# Zio_Eink_Display_Red_2_9.net
KiCad netlist of a schematic drawn in EAGLE
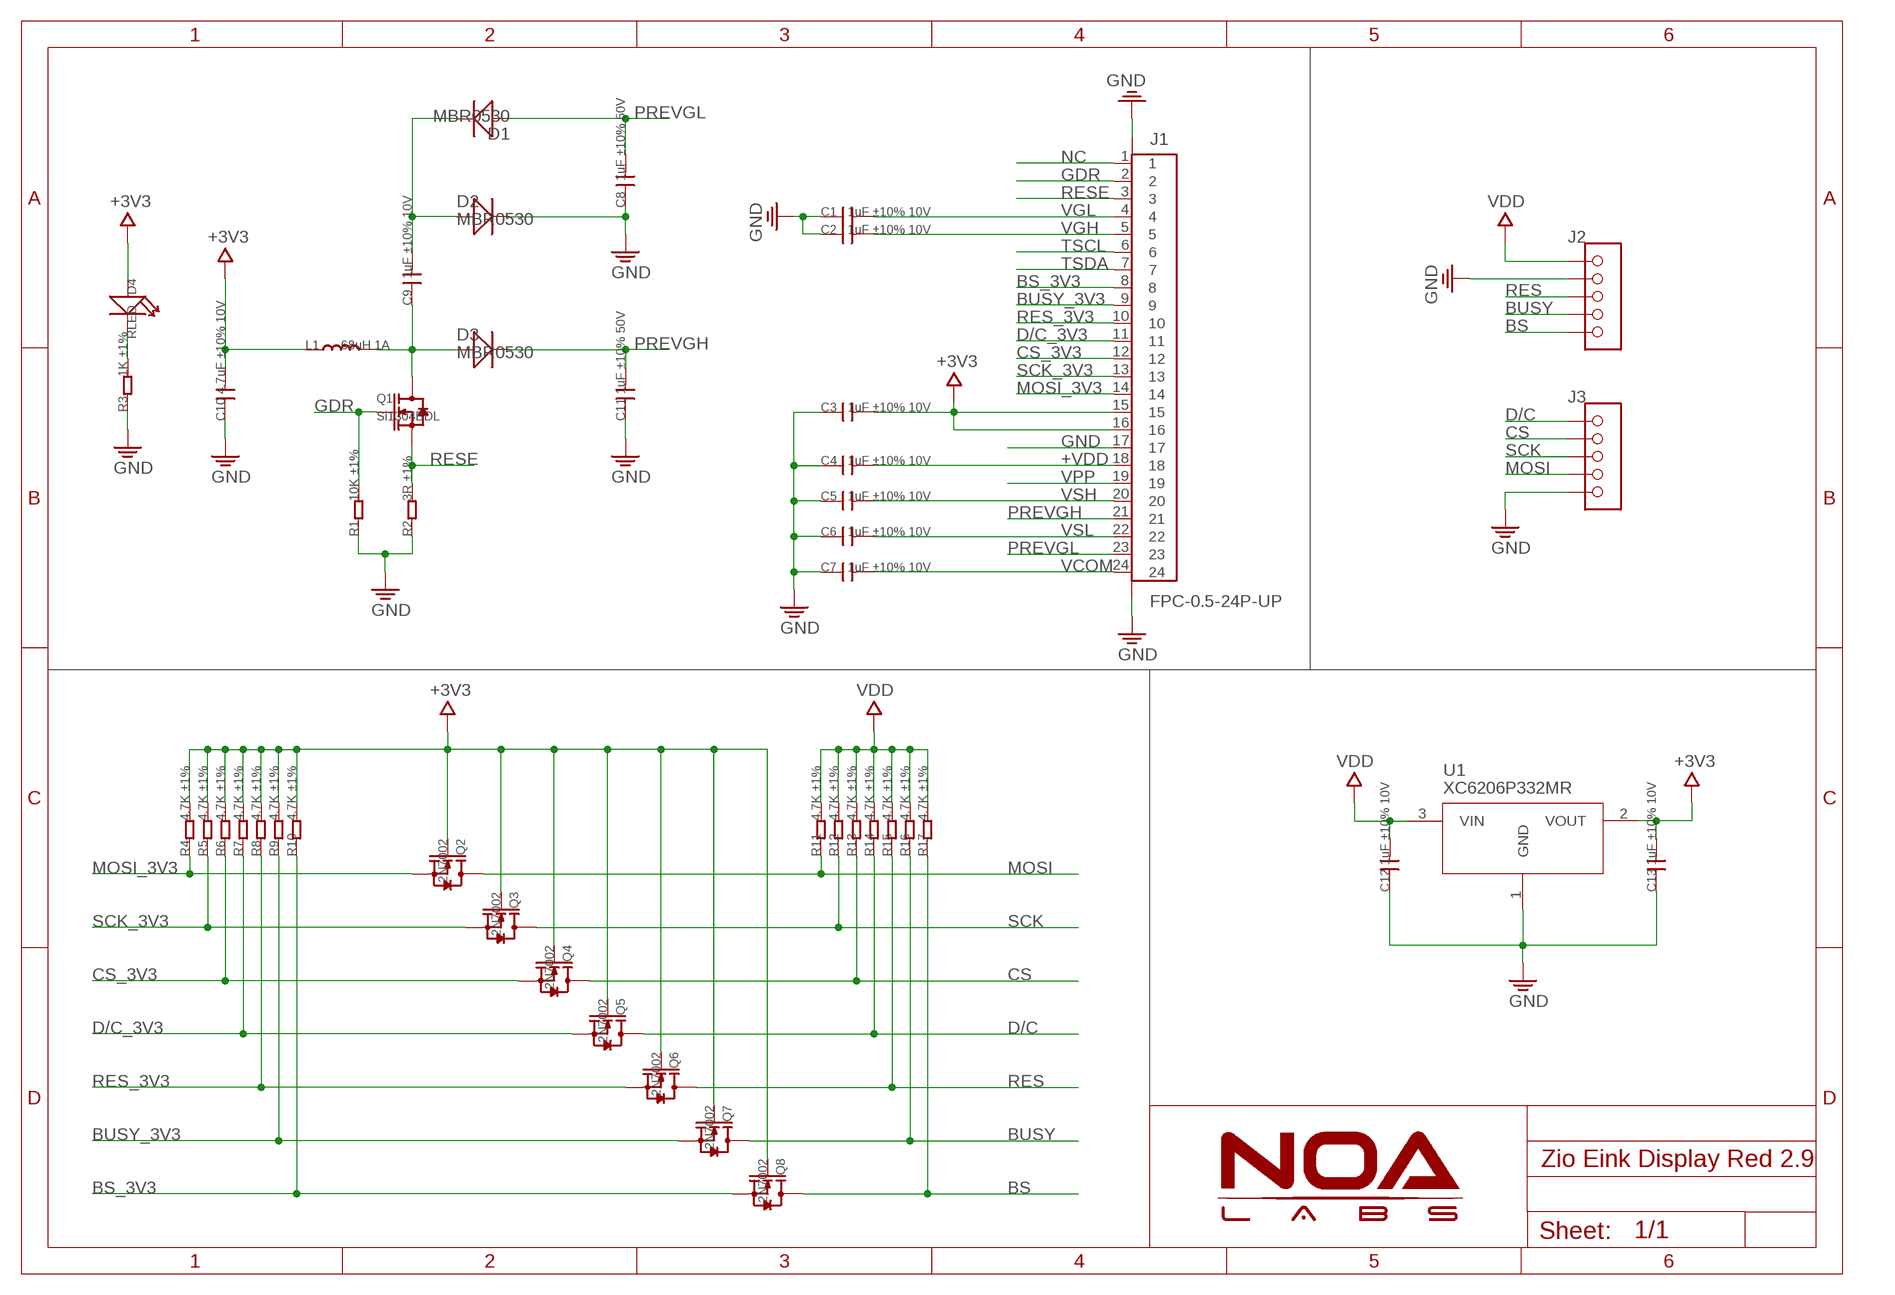
[diagram p0: schematic, sheet 1]

(export (version "E")
  (design (tool "Eeschema 10.0.6"))
  (components
    (comp (ref "C1")
      (value "1uF ±10% 10V")
      (footprint "eagle-import:0603")
      (libsource (lib "eagle-import") (part "C-0603"))
    )
    (comp (ref "C2")
      (value "1uF ±10% 10V")
      (footprint "eagle-import:0603")
      (libsource (lib "eagle-import") (part "C-0603"))
    )
    (comp (ref "C3")
      (value "1uF ±10% 10V")
      (footprint "eagle-import:0603")
      (libsource (lib "eagle-import") (part "C-0603"))
    )
    (comp (ref "C4")
      (value "1uF ±10% 10V")
      (footprint "eagle-import:0603")
      (libsource (lib "eagle-import") (part "C-0603"))
    )
    (comp (ref "C5")
      (value "1uF ±10% 10V")
      (footprint "eagle-import:0603")
      (libsource (lib "eagle-import") (part "C-0603"))
    )
    (comp (ref "C6")
      (value "1uF ±10% 10V")
      (footprint "eagle-import:0603")
      (libsource (lib "eagle-import") (part "C-0603"))
    )
    (comp (ref "C7")
      (value "1uF ±10% 10V")
      (footprint "eagle-import:0603")
      (libsource (lib "eagle-import") (part "C-0603"))
    )
    (comp (ref "C8")
      (value "1uF ±10% 50V")
      (footprint "eagle-import:0603")
      (libsource (lib "eagle-import") (part "C-0603"))
    )
    (comp (ref "C9")
      (value "1uF ±10% 10V")
      (footprint "eagle-import:0603")
      (libsource (lib "eagle-import") (part "C-0603"))
    )
    (comp (ref "C10")
      (value "4.7uF ±10% 10V")
      (footprint "eagle-import:0603")
      (libsource (lib "eagle-import") (part "C-0603"))
    )
    (comp (ref "C11")
      (value "1uF ±10% 50V")
      (footprint "eagle-import:0603")
      (libsource (lib "eagle-import") (part "C-0603"))
    )
    (comp (ref "C12")
      (value "1uF ±10% 10V")
      (footprint "eagle-import:0603")
      (libsource (lib "eagle-import") (part "C-0603"))
    )
    (comp (ref "C13")
      (value "1uF ±10% 10V")
      (footprint "eagle-import:0603")
      (libsource (lib "eagle-import") (part "C-0603"))
    )
    (comp (ref "D1")
      (value "MBR0530")
      (footprint "eagle-import:SOD123")
      (libsource (lib "eagle-import") (part "D'1206'"))
    )
    (comp (ref "D2")
      (value "MBR0530")
      (footprint "eagle-import:SOD123")
      (libsource (lib "eagle-import") (part "D'1206'"))
    )
    (comp (ref "D3")
      (value "MBR0530")
      (footprint "eagle-import:SOD123")
      (libsource (lib "eagle-import") (part "D'1206'"))
    )
    (comp (ref "D4")
      (value "RLED")
      (footprint "eagle-import:LED-0603")
      (libsource (lib "eagle-import") (part "LED'0603'"))
    )
    (comp (ref "J1")
      (value "FPC-0.5-24P-UP")
      (footprint "eagle-import:FPC-0.5-24P_UP")
      (libsource (lib "eagle-import") (part "FPC-0.5-24P-UP"))
    )
    (comp (ref "J2")
      (value "HEADER-5P-2.54")
      (footprint "eagle-import:5P-2.54")
      (libsource (lib "eagle-import") (part "HEADER-5P-2.54"))
    )
    (comp (ref "J3")
      (value "HEADER-5P-2.54")
      (footprint "eagle-import:5P-2.54")
      (libsource (lib "eagle-import") (part "HEADER-5P-2.54"))
    )
    (comp (ref "L1")
      (value "68uH 1A")
      (footprint "eagle-import:L3012")
      (libsource (lib "eagle-import") (part "L"))
    )
    (comp (ref "Q1")
      (value "Si1304BDL")
      (footprint "eagle-import:SOT-323")
      (libsource (lib "eagle-import") (part "MOSFET-N-323"))
    )
    (comp (ref "Q2")
      (value "2N7002")
      (footprint "eagle-import:SOT23")
      (libsource (lib "eagle-import") (part "MOSFET-N-SOT23"))
    )
    (comp (ref "Q3")
      (value "2N7002")
      (footprint "eagle-import:SOT23")
      (libsource (lib "eagle-import") (part "MOSFET-N-SOT23"))
    )
    (comp (ref "Q4")
      (value "2N7002")
      (footprint "eagle-import:SOT23")
      (libsource (lib "eagle-import") (part "MOSFET-N-SOT23"))
    )
    (comp (ref "Q5")
      (value "2N7002")
      (footprint "eagle-import:SOT23")
      (libsource (lib "eagle-import") (part "MOSFET-N-SOT23"))
    )
    (comp (ref "Q6")
      (value "2N7002")
      (footprint "eagle-import:SOT23")
      (libsource (lib "eagle-import") (part "MOSFET-N-SOT23"))
    )
    (comp (ref "Q7")
      (value "2N7002")
      (footprint "eagle-import:SOT23")
      (libsource (lib "eagle-import") (part "MOSFET-N-SOT23"))
    )
    (comp (ref "Q8")
      (value "2N7002")
      (footprint "eagle-import:SOT23")
      (libsource (lib "eagle-import") (part "MOSFET-N-SOT23"))
    )
    (comp (ref "R1")
      (value "10K ±1%")
      (footprint "eagle-import:0603")
      (libsource (lib "eagle-import") (part "R-0603"))
    )
    (comp (ref "R2")
      (value "3R ±1%")
      (footprint "eagle-import:0603")
      (libsource (lib "eagle-import") (part "R-0603"))
    )
    (comp (ref "R3")
      (value "1K ±1%")
      (footprint "eagle-import:0603")
      (libsource (lib "eagle-import") (part "R-0603"))
    )
    (comp (ref "R4")
      (value "4.7K ±1%")
      (footprint "eagle-import:0603")
      (libsource (lib "eagle-import") (part "R-0603"))
    )
    (comp (ref "R5")
      (value "4.7K ±1%")
      (footprint "eagle-import:0603")
      (libsource (lib "eagle-import") (part "R-0603"))
    )
    (comp (ref "R6")
      (value "4.7K ±1%")
      (footprint "eagle-import:0603")
      (libsource (lib "eagle-import") (part "R-0603"))
    )
    (comp (ref "R7")
      (value "4.7K ±1%")
      (footprint "eagle-import:0603")
      (libsource (lib "eagle-import") (part "R-0603"))
    )
    (comp (ref "R8")
      (value "4.7K ±1%")
      (footprint "eagle-import:0603")
      (libsource (lib "eagle-import") (part "R-0603"))
    )
    (comp (ref "R9")
      (value "4.7K ±1%")
      (footprint "eagle-import:0603")
      (libsource (lib "eagle-import") (part "R-0603"))
    )
    (comp (ref "R10")
      (value "4.7K ±1%")
      (footprint "eagle-import:0603")
      (libsource (lib "eagle-import") (part "R-0603"))
    )
    (comp (ref "R11")
      (value "4.7K ±1%")
      (footprint "eagle-import:0603")
      (libsource (lib "eagle-import") (part "R-0603"))
    )
    (comp (ref "R12")
      (value "4.7K ±1%")
      (footprint "eagle-import:0603")
      (libsource (lib "eagle-import") (part "R-0603"))
    )
    (comp (ref "R13")
      (value "4.7K ±1%")
      (footprint "eagle-import:0603")
      (libsource (lib "eagle-import") (part "R-0603"))
    )
    (comp (ref "R14")
      (value "4.7K ±1%")
      (footprint "eagle-import:0603")
      (libsource (lib "eagle-import") (part "R-0603"))
    )
    (comp (ref "R15")
      (value "4.7K ±1%")
      (footprint "eagle-import:0603")
      (libsource (lib "eagle-import") (part "R-0603"))
    )
    (comp (ref "R16")
      (value "4.7K ±1%")
      (footprint "eagle-import:0603")
      (libsource (lib "eagle-import") (part "R-0603"))
    )
    (comp (ref "R17")
      (value "4.7K ±1%")
      (footprint "eagle-import:0603")
      (libsource (lib "eagle-import") (part "R-0603"))
    )
    (comp (ref "U1")
      (value "XC6206P332MR")
      (footprint "eagle-import:SOT23")
      (libsource (lib "eagle-import") (part "XC6206MR"))
    )
  )
  (nets
    (net (code "1") (name "+3V3") (class "Default")
      (node (ref "C10") (pin "2") (pinfunction "2_2") (pintype "passive"))
      (node (ref "C13") (pin "2") (pinfunction "2_2") (pintype "passive"))
      (node (ref "C3") (pin "2") (pinfunction "2_2") (pintype "passive"))
      (node (ref "D4") (pin "+") (pinfunction "+_+") (pintype "passive"))
      (node (ref "J1") (pin "15") (pinfunction "15_15") (pintype "bidirectional"))
      (node (ref "J1") (pin "16") (pinfunction "16_16") (pintype "bidirectional"))
      (node (ref "L1") (pin "P$1") (pinfunction "1_P$1") (pintype "passive"))
      (node (ref "Q2") (pin "1") (pinfunction "G_1") (pintype "passive"))
      (node (ref "Q3") (pin "1") (pinfunction "G_1") (pintype "passive"))
      (node (ref "Q4") (pin "1") (pinfunction "G_1") (pintype "passive"))
      (node (ref "Q5") (pin "1") (pinfunction "G_1") (pintype "passive"))
      (node (ref "Q6") (pin "1") (pinfunction "G_1") (pintype "passive"))
      (node (ref "Q7") (pin "1") (pinfunction "G_1") (pintype "passive"))
      (node (ref "Q8") (pin "1") (pinfunction "G_1") (pintype "passive"))
      (node (ref "R10") (pin "2") (pinfunction "2_2") (pintype "passive"))
      (node (ref "R4") (pin "2") (pinfunction "2_2") (pintype "passive"))
      (node (ref "R5") (pin "2") (pinfunction "2_2") (pintype "passive"))
      (node (ref "R6") (pin "2") (pinfunction "2_2") (pintype "passive"))
      (node (ref "R7") (pin "2") (pinfunction "2_2") (pintype "passive"))
      (node (ref "R8") (pin "2") (pinfunction "2_2") (pintype "passive"))
      (node (ref "R9") (pin "2") (pinfunction "2_2") (pintype "passive"))
      (node (ref "U1") (pin "2") (pinfunction "VOUT_2") (pintype "bidirectional"))
    )
    (net (code "2") (name "/+VDD") (class "Default")
      (node (ref "C4") (pin "2") (pinfunction "2_2") (pintype "passive"))
      (node (ref "J1") (pin "18") (pinfunction "18_18") (pintype "bidirectional"))
    )
    (net (code "3") (name "/BS") (class "Default")
      (node (ref "J2") (pin "5") (pinfunction "5_5") (pintype "bidirectional"))
      (node (ref "Q8") (pin "3") (pinfunction "D_3") (pintype "passive"))
      (node (ref "R17") (pin "1") (pinfunction "1_1") (pintype "passive"))
    )
    (net (code "4") (name "/BS_3V3") (class "Default")
      (node (ref "J1") (pin "8") (pinfunction "8_8") (pintype "bidirectional"))
      (node (ref "Q8") (pin "2") (pinfunction "S_2") (pintype "passive"))
      (node (ref "R10") (pin "1") (pinfunction "1_1") (pintype "passive"))
    )
    (net (code "5") (name "/BUSY") (class "Default")
      (node (ref "J2") (pin "4") (pinfunction "4_4") (pintype "bidirectional"))
      (node (ref "Q7") (pin "3") (pinfunction "D_3") (pintype "passive"))
      (node (ref "R16") (pin "1") (pinfunction "1_1") (pintype "passive"))
    )
    (net (code "6") (name "/BUSY_3V3") (class "Default")
      (node (ref "J1") (pin "9") (pinfunction "9_9") (pintype "bidirectional"))
      (node (ref "Q7") (pin "2") (pinfunction "S_2") (pintype "passive"))
      (node (ref "R9") (pin "1") (pinfunction "1_1") (pintype "passive"))
    )
    (net (code "7") (name "/CS") (class "Default")
      (node (ref "J3") (pin "2") (pinfunction "2_2") (pintype "bidirectional"))
      (node (ref "Q4") (pin "3") (pinfunction "D_3") (pintype "passive"))
      (node (ref "R13") (pin "1") (pinfunction "1_1") (pintype "passive"))
    )
    (net (code "8") (name "/CS_3V3") (class "Default")
      (node (ref "J1") (pin "12") (pinfunction "12_12") (pintype "bidirectional"))
      (node (ref "Q4") (pin "2") (pinfunction "S_2") (pintype "passive"))
      (node (ref "R6") (pin "1") (pinfunction "1_1") (pintype "passive"))
    )
    (net (code "9") (name "/D{slash}C") (class "Default")
      (node (ref "J3") (pin "1") (pinfunction "1_1") (pintype "bidirectional"))
      (node (ref "Q5") (pin "3") (pinfunction "D_3") (pintype "passive"))
      (node (ref "R14") (pin "1") (pinfunction "1_1") (pintype "passive"))
    )
    (net (code "10") (name "/D{slash}C_3V3") (class "Default")
      (node (ref "J1") (pin "11") (pinfunction "11_11") (pintype "bidirectional"))
      (node (ref "Q5") (pin "2") (pinfunction "S_2") (pintype "passive"))
      (node (ref "R7") (pin "1") (pinfunction "1_1") (pintype "passive"))
    )
    (net (code "11") (name "/GDR") (class "Default")
      (node (ref "J1") (pin "2") (pinfunction "2_2") (pintype "bidirectional"))
      (node (ref "Q1") (pin "1") (pinfunction "G_1") (pintype "passive"))
      (node (ref "R1") (pin "2") (pinfunction "2_2") (pintype "passive"))
    )
    (net (code "12") (name "/MOSI") (class "Default")
      (node (ref "J3") (pin "4") (pinfunction "4_4") (pintype "bidirectional"))
      (node (ref "Q2") (pin "3") (pinfunction "D_3") (pintype "passive"))
      (node (ref "R11") (pin "1") (pinfunction "1_1") (pintype "passive"))
    )
    (net (code "13") (name "/MOSI_3V3") (class "Default")
      (node (ref "J1") (pin "14") (pinfunction "14_14") (pintype "bidirectional"))
      (node (ref "Q2") (pin "2") (pinfunction "S_2") (pintype "passive"))
      (node (ref "R4") (pin "1") (pinfunction "1_1") (pintype "passive"))
    )
    (net (code "14") (name "/NC") (class "Default")
      (node (ref "J1") (pin "1") (pinfunction "1_1") (pintype "bidirectional"))
    )
    (net (code "15") (name "/PREVGH") (class "Default")
      (node (ref "C11") (pin "2") (pinfunction "2_2") (pintype "passive"))
      (node (ref "D3") (pin "-") (pinfunction "-_-") (pintype "passive"))
      (node (ref "J1") (pin "21") (pinfunction "21_21") (pintype "bidirectional"))
    )
    (net (code "16") (name "/PREVGL") (class "Default")
      (node (ref "C8") (pin "2") (pinfunction "2_2") (pintype "passive"))
      (node (ref "D1") (pin "+") (pinfunction "+_+") (pintype "passive"))
      (node (ref "J1") (pin "23") (pinfunction "23_23") (pintype "bidirectional"))
    )
    (net (code "17") (name "/RES") (class "Default")
      (node (ref "J2") (pin "3") (pinfunction "3_3") (pintype "bidirectional"))
      (node (ref "Q6") (pin "3") (pinfunction "D_3") (pintype "passive"))
      (node (ref "R15") (pin "1") (pinfunction "1_1") (pintype "passive"))
    )
    (net (code "18") (name "/RESE") (class "Default")
      (node (ref "J1") (pin "3") (pinfunction "3_3") (pintype "bidirectional"))
      (node (ref "Q1") (pin "2") (pinfunction "S_2") (pintype "passive"))
      (node (ref "R2") (pin "2") (pinfunction "2_2") (pintype "passive"))
    )
    (net (code "19") (name "/RES_3V3") (class "Default")
      (node (ref "J1") (pin "10") (pinfunction "10_10") (pintype "bidirectional"))
      (node (ref "Q6") (pin "2") (pinfunction "S_2") (pintype "passive"))
      (node (ref "R8") (pin "1") (pinfunction "1_1") (pintype "passive"))
    )
    (net (code "20") (name "/SCK") (class "Default")
      (node (ref "J3") (pin "3") (pinfunction "3_3") (pintype "bidirectional"))
      (node (ref "Q3") (pin "3") (pinfunction "D_3") (pintype "passive"))
      (node (ref "R12") (pin "1") (pinfunction "1_1") (pintype "passive"))
    )
    (net (code "21") (name "/SCK_3V3") (class "Default")
      (node (ref "J1") (pin "13") (pinfunction "13_13") (pintype "bidirectional"))
      (node (ref "Q3") (pin "2") (pinfunction "S_2") (pintype "passive"))
      (node (ref "R5") (pin "1") (pinfunction "1_1") (pintype "passive"))
    )
    (net (code "22") (name "/TSCL") (class "Default")
      (node (ref "J1") (pin "6") (pinfunction "6_6") (pintype "bidirectional"))
    )
    (net (code "23") (name "/TSDA") (class "Default")
      (node (ref "J1") (pin "7") (pinfunction "7_7") (pintype "bidirectional"))
    )
    (net (code "24") (name "/VCOM") (class "Default")
      (node (ref "C7") (pin "2") (pinfunction "2_2") (pintype "passive"))
      (node (ref "J1") (pin "24") (pinfunction "24_24") (pintype "bidirectional"))
    )
    (net (code "25") (name "/VGH") (class "Default")
      (node (ref "C2") (pin "2") (pinfunction "2_2") (pintype "passive"))
      (node (ref "J1") (pin "5") (pinfunction "5_5") (pintype "bidirectional"))
    )
    (net (code "26") (name "/VGL") (class "Default")
      (node (ref "C1") (pin "2") (pinfunction "2_2") (pintype "passive"))
      (node (ref "J1") (pin "4") (pinfunction "4_4") (pintype "bidirectional"))
    )
    (net (code "27") (name "/VPP") (class "Default")
      (node (ref "J1") (pin "19") (pinfunction "19_19") (pintype "bidirectional"))
    )
    (net (code "28") (name "/VSH") (class "Default")
      (node (ref "C5") (pin "2") (pinfunction "2_2") (pintype "passive"))
      (node (ref "J1") (pin "20") (pinfunction "20_20") (pintype "bidirectional"))
    )
    (net (code "29") (name "/VSL") (class "Default")
      (node (ref "C6") (pin "2") (pinfunction "2_2") (pintype "passive"))
      (node (ref "J1") (pin "22") (pinfunction "22_22") (pintype "bidirectional"))
    )
    (net (code "30") (name "GND") (class "Default")
      (node (ref "C1") (pin "1") (pinfunction "1_1") (pintype "passive"))
      (node (ref "C10") (pin "1") (pinfunction "1_1") (pintype "passive"))
      (node (ref "C11") (pin "1") (pinfunction "1_1") (pintype "passive"))
      (node (ref "C12") (pin "1") (pinfunction "1_1") (pintype "passive"))
      (node (ref "C13") (pin "1") (pinfunction "1_1") (pintype "passive"))
      (node (ref "C2") (pin "1") (pinfunction "1_1") (pintype "passive"))
      (node (ref "C3") (pin "1") (pinfunction "1_1") (pintype "passive"))
      (node (ref "C4") (pin "1") (pinfunction "1_1") (pintype "passive"))
      (node (ref "C5") (pin "1") (pinfunction "1_1") (pintype "passive"))
      (node (ref "C6") (pin "1") (pinfunction "1_1") (pintype "passive"))
      (node (ref "C7") (pin "1") (pinfunction "1_1") (pintype "passive"))
      (node (ref "C8") (pin "1") (pinfunction "1_1") (pintype "passive"))
      (node (ref "D2") (pin "-") (pinfunction "-_-") (pintype "passive"))
      (node (ref "J1") (pin "17") (pinfunction "17_17") (pintype "bidirectional"))
      (node (ref "J1") (pin "25") (pinfunction "G1_25") (pintype "bidirectional"))
      (node (ref "J1") (pin "26") (pinfunction "G2_26") (pintype "bidirectional"))
      (node (ref "J2") (pin "2") (pinfunction "2_2") (pintype "bidirectional"))
      (node (ref "J3") (pin "5") (pinfunction "5_5") (pintype "bidirectional"))
      (node (ref "R1") (pin "1") (pinfunction "1_1") (pintype "passive"))
      (node (ref "R2") (pin "1") (pinfunction "1_1") (pintype "passive"))
      (node (ref "R3") (pin "1") (pinfunction "1_1") (pintype "passive"))
      (node (ref "U1") (pin "1") (pinfunction "GND_1") (pintype "bidirectional"))
    )
    (net (code "31") (name "Net-(C9-Pad2)") (class "Default")
      (node (ref "C9") (pin "2") (pinfunction "2_2") (pintype "passive"))
      (node (ref "D1") (pin "-") (pinfunction "-_-") (pintype "passive"))
      (node (ref "D2") (pin "+") (pinfunction "+_+") (pintype "passive"))
    )
    (net (code "32") (name "Net-(D4-Pad-)") (class "Default")
      (node (ref "D4") (pin "-") (pinfunction "-_-") (pintype "passive"))
      (node (ref "R3") (pin "2") (pinfunction "2_2") (pintype "passive"))
    )
    (net (code "33") (name "Net-(L1-2)") (class "Default")
      (node (ref "C9") (pin "1") (pinfunction "1_1") (pintype "passive"))
      (node (ref "D3") (pin "+") (pinfunction "+_+") (pintype "passive"))
      (node (ref "L1") (pin "P$2") (pinfunction "2_P$2") (pintype "passive"))
      (node (ref "Q1") (pin "3") (pinfunction "D_3") (pintype "passive"))
    )
    (net (code "34") (name "VDD") (class "Default")
      (node (ref "C12") (pin "2") (pinfunction "2_2") (pintype "passive"))
      (node (ref "J2") (pin "1") (pinfunction "1_1") (pintype "bidirectional"))
      (node (ref "R11") (pin "2") (pinfunction "2_2") (pintype "passive"))
      (node (ref "R12") (pin "2") (pinfunction "2_2") (pintype "passive"))
      (node (ref "R13") (pin "2") (pinfunction "2_2") (pintype "passive"))
      (node (ref "R14") (pin "2") (pinfunction "2_2") (pintype "passive"))
      (node (ref "R15") (pin "2") (pinfunction "2_2") (pintype "passive"))
      (node (ref "R16") (pin "2") (pinfunction "2_2") (pintype "passive"))
      (node (ref "R17") (pin "2") (pinfunction "2_2") (pintype "passive"))
      (node (ref "U1") (pin "3") (pinfunction "VIN_3") (pintype "bidirectional"))
    )
  )
)
